# avr_g1000r_24.net
KiCad netlist of a schematic drawn in EAGLE
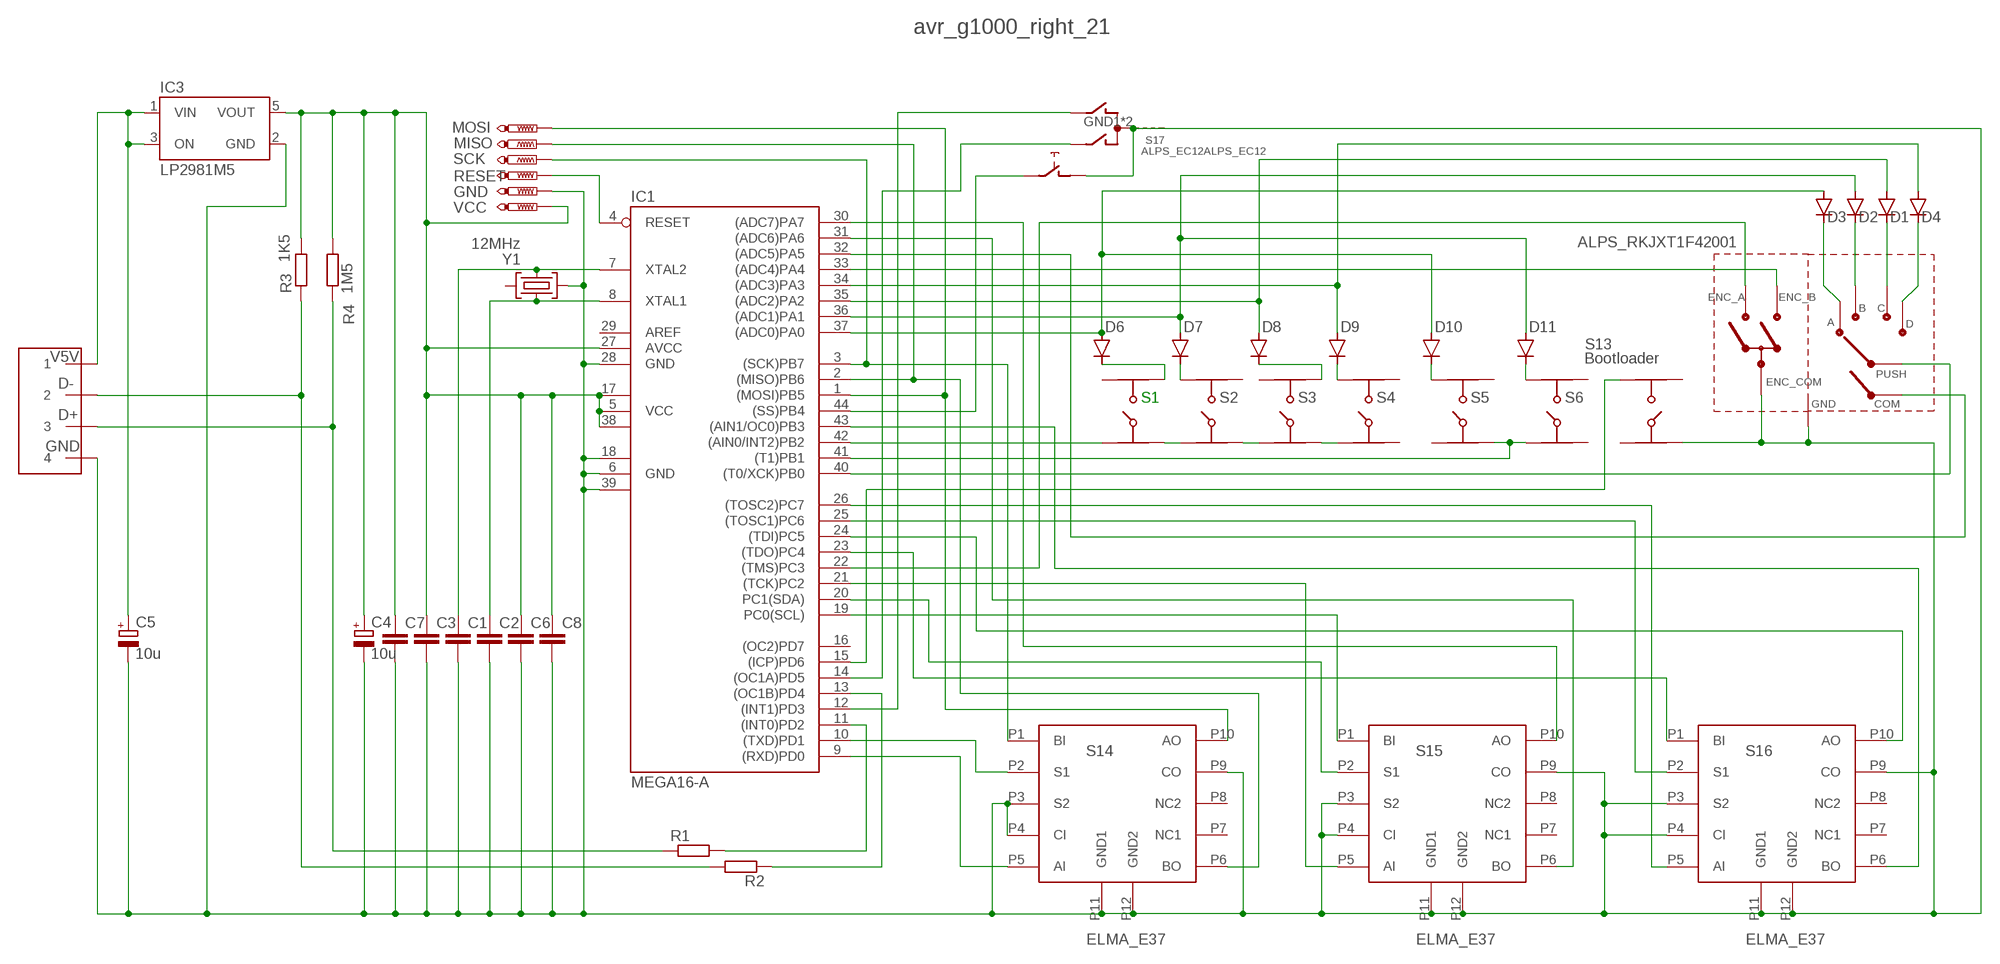
[diagram p0: schematic, sheet 1]

(export (version "E")
  (design (tool "Eeschema 10.0.6"))
  (components
    (comp (ref "C1")
      (value "C-EUC0402")
      (footprint "eagle-import:C0402")
      (libsource (lib "eagle-import") (part "C-EUC0402"))
    )
    (comp (ref "C2")
      (value "C-EUC0402")
      (footprint "eagle-import:C0402")
      (libsource (lib "eagle-import") (part "C-EUC0402"))
    )
    (comp (ref "C3")
      (value "C-EUC0402")
      (footprint "eagle-import:C0402")
      (libsource (lib "eagle-import") (part "C-EUC0402"))
    )
    (comp (ref "C4")
      (value "10u")
      (footprint "eagle-import:SMC_A")
      (libsource (lib "eagle-import") (part "CPOL-EUSMCA"))
    )
    (comp (ref "C5")
      (value "10u")
      (footprint "eagle-import:SMC_A")
      (libsource (lib "eagle-import") (part "CPOL-EUSMCA"))
    )
    (comp (ref "C6")
      (value "C-EUC0402")
      (footprint "eagle-import:C0402")
      (libsource (lib "eagle-import") (part "C-EUC0402"))
    )
    (comp (ref "C7")
      (value "C-EUC0402")
      (footprint "eagle-import:C0402")
      (libsource (lib "eagle-import") (part "C-EUC0402"))
    )
    (comp (ref "C8")
      (value "C-EUC0402")
      (footprint "eagle-import:C0402")
      (libsource (lib "eagle-import") (part "C-EUC0402"))
    )
    (comp (ref "D1")
      (value "DIODE-SOD123")
      (footprint "eagle-import:SOD123")
      (fields (field (name "SPICEPREFIX") "D"))
      (libsource (lib "eagle-import") (part "DIODE-SOD123"))
    )
    (comp (ref "D2")
      (value "DIODE-SOD123")
      (footprint "eagle-import:SOD123")
      (fields (field (name "SPICEPREFIX") "D"))
      (libsource (lib "eagle-import") (part "DIODE-SOD123"))
    )
    (comp (ref "D3")
      (value "DIODE-SOD123")
      (footprint "eagle-import:SOD123")
      (fields (field (name "SPICEPREFIX") "D"))
      (libsource (lib "eagle-import") (part "DIODE-SOD123"))
    )
    (comp (ref "D4")
      (value "DIODE-SOD123")
      (footprint "eagle-import:SOD123")
      (fields (field (name "SPICEPREFIX") "D"))
      (libsource (lib "eagle-import") (part "DIODE-SOD123"))
    )
    (comp (ref "D6")
      (value "DIODE-SOD123")
      (footprint "eagle-import:SOD123")
      (fields (field (name "SPICEPREFIX") "D"))
      (libsource (lib "eagle-import") (part "DIODE-SOD123"))
    )
    (comp (ref "D7")
      (value "DIODE-SOD123")
      (footprint "eagle-import:SOD123")
      (fields (field (name "SPICEPREFIX") "D"))
      (libsource (lib "eagle-import") (part "DIODE-SOD123"))
    )
    (comp (ref "D8")
      (value "DIODE-SOD123")
      (footprint "eagle-import:SOD123")
      (fields (field (name "SPICEPREFIX") "D"))
      (libsource (lib "eagle-import") (part "DIODE-SOD123"))
    )
    (comp (ref "D9")
      (value "DIODE-SOD123")
      (footprint "eagle-import:SOD123")
      (fields (field (name "SPICEPREFIX") "D"))
      (libsource (lib "eagle-import") (part "DIODE-SOD123"))
    )
    (comp (ref "D10")
      (value "DIODE-SOD123")
      (footprint "eagle-import:SOD123")
      (fields (field (name "SPICEPREFIX") "D"))
      (libsource (lib "eagle-import") (part "DIODE-SOD123"))
    )
    (comp (ref "D11")
      (value "DIODE-SOD123")
      (footprint "eagle-import:SOD123")
      (fields (field (name "SPICEPREFIX") "D"))
      (libsource (lib "eagle-import") (part "DIODE-SOD123"))
    )
    (comp (ref "GND")
      (value "PTR1TP10R")
      (footprint "eagle-import:TP10R")
      (libsource (lib "eagle-import") (part "PTR1TP10R"))
    )
    (comp (ref "IC1")
      (value "MEGA16-A")
      (footprint "eagle-import:TQFP44")
      (fields (field (name "MPN") "ATMEGA16-16AU"))
      (libsource (lib "eagle-import") (part "MEGA16-A"))
    )
    (comp (ref "IC3")
      (value "LP2981M5")
      (footprint "eagle-import:SOT23-5")
      (libsource (lib "eagle-import") (part "LP2981M5"))
    )
    (comp (ref "MISO")
      (value "PTR1TP10R")
      (footprint "eagle-import:TP10R")
      (libsource (lib "eagle-import") (part "PTR1TP10R"))
    )
    (comp (ref "MOSI")
      (value "PTR1TP10R")
      (footprint "eagle-import:TP10R")
      (libsource (lib "eagle-import") (part "PTR1TP10R"))
    )
    (comp (ref "R1")
      (value "R-EU_R0603")
      (footprint "eagle-import:R0603")
      (libsource (lib "eagle-import") (part "R-EU_R0603"))
    )
    (comp (ref "R2")
      (value "R-EU_R0603")
      (footprint "eagle-import:R0603")
      (libsource (lib "eagle-import") (part "R-EU_R0603"))
    )
    (comp (ref "R3")
      (value "1K5")
      (footprint "eagle-import:R0603")
      (libsource (lib "eagle-import") (part "R-EU_R0603"))
    )
    (comp (ref "R4")
      (value "1M5")
      (footprint "eagle-import:R0603")
      (libsource (lib "eagle-import") (part "R-EU_R0603"))
    )
    (comp (ref "RESET")
      (value "PTR1TP10R")
      (footprint "eagle-import:TP10R")
      (libsource (lib "eagle-import") (part "PTR1TP10R"))
    )
    (comp (ref "S1")
      (value "B3FS1000")
      (footprint "eagle-import:B3FS1000")
      (fields (field (name "SPICEPREFIX") "S"))
      (libsource (lib "eagle-import") (part "B3FS1000"))
    )
    (comp (ref "S2")
      (value "B3FS1000")
      (footprint "eagle-import:B3FS1000")
      (libsource (lib "eagle-import") (part "B3FS1000"))
    )
    (comp (ref "S3")
      (value "B3FS1000")
      (footprint "eagle-import:B3FS1000")
      (libsource (lib "eagle-import") (part "B3FS1000"))
    )
    (comp (ref "S4")
      (value "B3FS1000")
      (footprint "eagle-import:B3FS1000")
      (libsource (lib "eagle-import") (part "B3FS1000"))
    )
    (comp (ref "S5")
      (value "B3FS1000")
      (footprint "eagle-import:B3FS1000")
      (libsource (lib "eagle-import") (part "B3FS1000"))
    )
    (comp (ref "S6")
      (value "B3FS1000")
      (footprint "eagle-import:B3FS1000")
      (libsource (lib "eagle-import") (part "B3FS1000"))
    )
    (comp (ref "S7")
      (value "RKJXT1F42001")
      (footprint "eagle-import:RKJXT1F42001")
      (libsource (lib "eagle-import") (part "RKJXT1F42001"))
    )
    (comp (ref "S13")
      (value "Bootloader")
      (footprint "eagle-import:B3FS1000")
      (libsource (lib "eagle-import") (part "B3FS1000"))
    )
    (comp (ref "S14")
      (value "ELMA_E37")
      (footprint "eagle-import:ELMA_E37")
      (libsource (lib "eagle-import") (part "ELMA_E37"))
    )
    (comp (ref "S15")
      (value "ELMA_E37")
      (footprint "eagle-import:ELMA_E37")
      (libsource (lib "eagle-import") (part "ELMA_E37"))
    )
    (comp (ref "S16")
      (value "ELMA_E37")
      (footprint "eagle-import:ELMA_E37")
      (libsource (lib "eagle-import") (part "ELMA_E37"))
    )
    (comp (ref "S17")
      (value "ALPS_EC12ALPS_EC12")
      (footprint "eagle-import:ALPS_EC12E_SW")
      (libsource (lib "eagle-import") (part "ALPS_EC12ALPS_EC12"))
    )
    (comp (ref "SCK")
      (value "PTR1TP10R")
      (footprint "eagle-import:TP10R")
      (libsource (lib "eagle-import") (part "PTR1TP10R"))
    )
    (comp (ref "U$4")
      (value "HEADER4X1.27")
      (footprint "eagle-import:HEADER4X1.27")
      (libsource (lib "eagle-import") (part "HEADER4X1.27"))
    )
    (comp (ref "VCC")
      (value "PTR1TP10R")
      (footprint "eagle-import:TP10R")
      (libsource (lib "eagle-import") (part "PTR1TP10R"))
    )
    (comp (ref "Y1")
      (value "12MHz")
      (footprint "eagle-import:OSCCC500X320X100")
      (libsource (lib "eagle-import") (part "MJ-CRYSTALMJ"))
    )
  )
  (nets
    (net (code "1") (name "/D+") (class "Default")
      (node (ref "R1") (pin "1") (pinfunction "1_1") (pintype "passive"))
      (node (ref "R4") (pin "1") (pinfunction "1_1") (pintype "passive"))
      (node (ref "U$4") (pin "P3") (pinfunction "3_P3") (pintype "bidirectional"))
    )
    (net (code "2") (name "/D-") (class "Default")
      (node (ref "R2") (pin "2") (pinfunction "2_2") (pintype "passive"))
      (node (ref "R3") (pin "1") (pinfunction "1_1") (pintype "passive"))
      (node (ref "U$4") (pin "P2") (pinfunction "2_P2") (pintype "bidirectional"))
    )
    (net (code "3") (name "/GND") (class "Default")
      (node (ref "C1") (pin "2") (pinfunction "2_2") (pintype "passive"))
      (node (ref "C2") (pin "2") (pinfunction "2_2") (pintype "passive"))
      (node (ref "C3") (pin "2") (pinfunction "2_2") (pintype "passive"))
      (node (ref "C4") (pin "-") (pinfunction "-_-") (pintype "passive"))
      (node (ref "C5") (pin "-") (pinfunction "-_-") (pintype "passive"))
      (node (ref "C6") (pin "2") (pinfunction "2_2") (pintype "passive"))
      (node (ref "C7") (pin "2") (pinfunction "2_2") (pintype "passive"))
      (node (ref "C8") (pin "2") (pinfunction "2_2") (pintype "passive"))
      (node (ref "GND") (pin "TP") (pinfunction "TP_TP") (pintype "input"))
      (node (ref "IC1") (pin "18") (pinfunction "GND1_18") (pintype "power_in"))
      (node (ref "IC1") (pin "28") (pinfunction "GND_28") (pintype "power_in"))
      (node (ref "IC1") (pin "39") (pinfunction "GND2_39") (pintype "power_in"))
      (node (ref "IC1") (pin "6") (pinfunction "GND_6") (pintype "power_in"))
      (node (ref "IC3") (pin "2") (pinfunction "GND_2") (pintype "power_in"))
      (node (ref "S13") (pin "3") (pinfunction "3_3") (pintype "passive"))
      (node (ref "S14") (pin "P11") (pinfunction "GND1_P11") (pintype "bidirectional"))
      (node (ref "S14") (pin "P12") (pinfunction "GND2_P12") (pintype "bidirectional"))
      (node (ref "S14") (pin "P3") (pinfunction "S2_P3") (pintype "bidirectional"))
      (node (ref "S14") (pin "P4") (pinfunction "CI_P4") (pintype "bidirectional"))
      (node (ref "S14") (pin "P9") (pinfunction "CO_P9") (pintype "bidirectional"))
      (node (ref "S15") (pin "P11") (pinfunction "GND1_P11") (pintype "bidirectional"))
      (node (ref "S15") (pin "P12") (pinfunction "GND2_P12") (pintype "bidirectional"))
      (node (ref "S15") (pin "P3") (pinfunction "S2_P3") (pintype "bidirectional"))
      (node (ref "S15") (pin "P4") (pinfunction "CI_P4") (pintype "bidirectional"))
      (node (ref "S15") (pin "P9") (pinfunction "CO_P9") (pintype "bidirectional"))
      (node (ref "S16") (pin "P11") (pinfunction "GND1_P11") (pintype "bidirectional"))
      (node (ref "S16") (pin "P12") (pinfunction "GND2_P12") (pintype "bidirectional"))
      (node (ref "S16") (pin "P3") (pinfunction "S2_P3") (pintype "bidirectional"))
      (node (ref "S16") (pin "P4") (pinfunction "CI_P4") (pintype "bidirectional"))
      (node (ref "S16") (pin "P9") (pinfunction "CO_P9") (pintype "bidirectional"))
      (node (ref "S17") (pin "C") (pinfunction "C_C") (pintype "passive"))
      (node (ref "S17") (pin "D") (pinfunction "1_D") (pintype "passive"))
      (node (ref "S17") (pin "GND1") (pinfunction "G_GND1") (pintype "passive"))
      (node (ref "S17") (pin "GND2") (pinfunction "G_GND2") (pintype "passive"))
      (node (ref "S7") (pin "ENC_COM") (pinfunction "ENC_COM_ENC_COM") (pintype "passive"))
      (node (ref "S7") (pin "GND") (pinfunction "GND_GND") (pintype "passive"))
      (node (ref "U$4") (pin "P4") (pinfunction "4_P4") (pintype "bidirectional"))
      (node (ref "Y1") (pin "2") (pinfunction "GND1_2") (pintype "bidirectional"))
    )
    (net (code "4") (name "/PB2") (class "Default")
      (node (ref "IC1") (pin "42") (pinfunction "(AIN0/INT2)PB2_42") (pintype "bidirectional"))
      (node (ref "S1") (pin "3") (pinfunction "3_3") (pintype "passive"))
      (node (ref "S1") (pin "4") (pinfunction "4_4") (pintype "passive"))
      (node (ref "S2") (pin "3") (pinfunction "3_3") (pintype "passive"))
      (node (ref "S2") (pin "4") (pinfunction "4_4") (pintype "passive"))
      (node (ref "S3") (pin "3") (pinfunction "3_3") (pintype "passive"))
      (node (ref "S3") (pin "4") (pinfunction "4_4") (pintype "passive"))
      (node (ref "S4") (pin "3") (pinfunction "3_3") (pintype "passive"))
    )
    (net (code "5") (name "/V5V") (class "Default")
      (node (ref "C5") (pin "+") (pinfunction "+_+") (pintype "passive"))
      (node (ref "IC3") (pin "1") (pinfunction "VIN_1") (pintype "power_in"))
      (node (ref "IC3") (pin "3") (pinfunction "ON_3") (pintype "input"))
      (node (ref "U$4") (pin "P1") (pinfunction "1_P1") (pintype "bidirectional"))
    )
    (net (code "6") (name "Net-(D1-PadC)") (class "Default")
      (node (ref "D1") (pin "C") (pinfunction "C_C") (pintype "passive"))
      (node (ref "S7") (pin "C") (pinfunction "C_C") (pintype "passive"))
    )
    (net (code "7") (name "Net-(D2-PadC)") (class "Default")
      (node (ref "D2") (pin "C") (pinfunction "C_C") (pintype "passive"))
      (node (ref "S7") (pin "B") (pinfunction "B_B") (pintype "passive"))
    )
    (net (code "8") (name "Net-(D3-PadC)") (class "Default")
      (node (ref "D3") (pin "C") (pinfunction "C_C") (pintype "passive"))
      (node (ref "S7") (pin "A") (pinfunction "A_A") (pintype "passive"))
    )
    (net (code "9") (name "Net-(D4-PadC)") (class "Default")
      (node (ref "D4") (pin "C") (pinfunction "C_C") (pintype "passive"))
      (node (ref "S7") (pin "D") (pinfunction "D_D") (pintype "passive"))
    )
    (net (code "10") (name "Net-(D6-PadC)") (class "Default")
      (node (ref "D6") (pin "C") (pinfunction "C_C") (pintype "passive"))
      (node (ref "S1") (pin "2") (pinfunction "2_2") (pintype "passive"))
    )
    (net (code "11") (name "Net-(D7-PadC)") (class "Default")
      (node (ref "D7") (pin "C") (pinfunction "C_C") (pintype "passive"))
      (node (ref "S2") (pin "1") (pinfunction "1_1") (pintype "passive"))
    )
    (net (code "12") (name "Net-(D8-PadC)") (class "Default")
      (node (ref "D8") (pin "C") (pinfunction "C_C") (pintype "passive"))
      (node (ref "S3") (pin "2") (pinfunction "2_2") (pintype "passive"))
    )
    (net (code "13") (name "Net-(D9-PadC)") (class "Default")
      (node (ref "D9") (pin "C") (pinfunction "C_C") (pintype "passive"))
      (node (ref "S4") (pin "1") (pinfunction "1_1") (pintype "passive"))
    )
    (net (code "14") (name "Net-(D10-PadC)") (class "Default")
      (node (ref "D10") (pin "C") (pinfunction "C_C") (pintype "passive"))
      (node (ref "S5") (pin "1") (pinfunction "1_1") (pintype "passive"))
    )
    (net (code "15") (name "Net-(D11-PadC)") (class "Default")
      (node (ref "D11") (pin "C") (pinfunction "C_C") (pintype "passive"))
      (node (ref "S6") (pin "1") (pinfunction "1_1") (pintype "passive"))
    )
    (net (code "16") (name "Net-(IC1-(ADC0)PA0)") (class "Default")
      (node (ref "D10") (pin "A") (pinfunction "A_A") (pintype "passive"))
      (node (ref "D3") (pin "A") (pinfunction "A_A") (pintype "passive"))
      (node (ref "D6") (pin "A") (pinfunction "A_A") (pintype "passive"))
      (node (ref "IC1") (pin "37") (pinfunction "(ADC0)PA0_37") (pintype "bidirectional"))
    )
    (net (code "17") (name "Net-(IC1-(ADC1)PA1)") (class "Default")
      (node (ref "D11") (pin "A") (pinfunction "A_A") (pintype "passive"))
      (node (ref "D2") (pin "A") (pinfunction "A_A") (pintype "passive"))
      (node (ref "D7") (pin "A") (pinfunction "A_A") (pintype "passive"))
      (node (ref "IC1") (pin "36") (pinfunction "(ADC1)PA1_36") (pintype "bidirectional"))
    )
    (net (code "18") (name "Net-(IC1-(ADC2)PA2)") (class "Default")
      (node (ref "D1") (pin "A") (pinfunction "A_A") (pintype "passive"))
      (node (ref "D8") (pin "A") (pinfunction "A_A") (pintype "passive"))
      (node (ref "IC1") (pin "35") (pinfunction "(ADC2)PA2_35") (pintype "bidirectional"))
    )
    (net (code "19") (name "Net-(IC1-(ADC3)PA3)") (class "Default")
      (node (ref "D4") (pin "A") (pinfunction "A_A") (pintype "passive"))
      (node (ref "D9") (pin "A") (pinfunction "A_A") (pintype "passive"))
      (node (ref "IC1") (pin "34") (pinfunction "(ADC3)PA3_34") (pintype "bidirectional"))
    )
    (net (code "20") (name "Net-(IC1-(ADC4)PA4)") (class "Default")
      (node (ref "IC1") (pin "33") (pinfunction "(ADC4)PA4_33") (pintype "bidirectional"))
      (node (ref "S7") (pin "ENC_B") (pinfunction "ENC_B_ENC_B") (pintype "passive"))
    )
    (net (code "21") (name "Net-(IC1-(ADC5)PA5)") (class "Default")
      (node (ref "IC1") (pin "32") (pinfunction "(ADC5)PA5_32") (pintype "bidirectional"))
      (node (ref "S7") (pin "COM") (pinfunction "COM_COM") (pintype "passive"))
    )
    (net (code "22") (name "Net-(IC1-(ADC6)PA6)") (class "Default")
      (node (ref "IC1") (pin "31") (pinfunction "(ADC6)PA6_31") (pintype "bidirectional"))
      (node (ref "S15") (pin "P6") (pinfunction "BO_P6") (pintype "bidirectional"))
    )
    (net (code "23") (name "Net-(IC1-(ADC7)PA7)") (class "Default")
      (node (ref "IC1") (pin "30") (pinfunction "(ADC7)PA7_30") (pintype "bidirectional"))
      (node (ref "S15") (pin "P10") (pinfunction "AO_P10") (pintype "bidirectional"))
    )
    (net (code "24") (name "Net-(IC1-(AIN1{slash}OC0)PB3)") (class "Default")
      (node (ref "IC1") (pin "43") (pinfunction "(AIN1/OC0)PB3_43") (pintype "bidirectional"))
      (node (ref "S16") (pin "P6") (pinfunction "BO_P6") (pintype "bidirectional"))
    )
    (net (code "25") (name "Net-(IC1-(ICP)PD6)") (class "Default")
      (node (ref "IC1") (pin "15") (pinfunction "(ICP)PD6_15") (pintype "bidirectional"))
      (node (ref "S13") (pin "2") (pinfunction "2_2") (pintype "passive"))
    )
    (net (code "26") (name "Net-(IC1-(INT0)PD2)") (class "Default")
      (node (ref "IC1") (pin "11") (pinfunction "(INT0)PD2_11") (pintype "bidirectional"))
      (node (ref "R1") (pin "2") (pinfunction "2_2") (pintype "passive"))
    )
    (net (code "27") (name "Net-(IC1-(INT1)PD3)") (class "Default")
      (node (ref "IC1") (pin "12") (pinfunction "(INT1)PD3_12") (pintype "bidirectional"))
      (node (ref "S17") (pin "B") (pinfunction "B_B") (pintype "passive"))
    )
    (net (code "28") (name "Net-(IC1-(MISO)PB6)") (class "Default")
      (node (ref "IC1") (pin "2") (pinfunction "(MISO)PB6_2") (pintype "bidirectional"))
      (node (ref "MISO") (pin "TP") (pinfunction "TP_TP") (pintype "input"))
      (node (ref "S14") (pin "P6") (pinfunction "BO_P6") (pintype "bidirectional"))
    )
    (net (code "29") (name "Net-(IC1-(MOSI)PB5)") (class "Default")
      (node (ref "IC1") (pin "1") (pinfunction "(MOSI)PB5_1") (pintype "bidirectional"))
      (node (ref "MOSI") (pin "TP") (pinfunction "TP_TP") (pintype "input"))
      (node (ref "S14") (pin "P10") (pinfunction "AO_P10") (pintype "bidirectional"))
    )
    (net (code "30") (name "Net-(IC1-(OC1A)PD5)") (class "Default")
      (node (ref "IC1") (pin "14") (pinfunction "(OC1A)PD5_14") (pintype "bidirectional"))
      (node (ref "S17") (pin "A") (pinfunction "A_A") (pintype "passive"))
    )
    (net (code "31") (name "Net-(IC1-(OC1B)PD4)") (class "Default")
      (node (ref "IC1") (pin "13") (pinfunction "(OC1B)PD4_13") (pintype "bidirectional"))
      (node (ref "R2") (pin "1") (pinfunction "1_1") (pintype "passive"))
    )
    (net (code "32") (name "Net-(IC1-(RXD)PD0)") (class "Default")
      (node (ref "IC1") (pin "9") (pinfunction "(RXD)PD0_9") (pintype "bidirectional"))
      (node (ref "S14") (pin "P5") (pinfunction "AI_P5") (pintype "bidirectional"))
    )
    (net (code "33") (name "Net-(IC1-(SCK)PB7)") (class "Default")
      (node (ref "IC1") (pin "3") (pinfunction "(SCK)PB7_3") (pintype "bidirectional"))
      (node (ref "S14") (pin "P1") (pinfunction "BI_P1") (pintype "bidirectional"))
      (node (ref "SCK") (pin "TP") (pinfunction "TP_TP") (pintype "input"))
    )
    (net (code "34") (name "Net-(IC1-(SS)PB4)") (class "Default")
      (node (ref "IC1") (pin "44") (pinfunction "(SS)PB4_44") (pintype "bidirectional"))
      (node (ref "S17") (pin "E") (pinfunction "2_E") (pintype "passive"))
    )
    (net (code "35") (name "Net-(IC1-(T0{slash}XCK)PB0)") (class "Default")
      (node (ref "IC1") (pin "40") (pinfunction "(T0/XCK)PB0_40") (pintype "bidirectional"))
      (node (ref "S7") (pin "PUSH") (pinfunction "PUSH_PUSH") (pintype "passive"))
    )
    (net (code "36") (name "Net-(IC1-(T1)PB1)") (class "Default")
      (node (ref "IC1") (pin "41") (pinfunction "(T1)PB1_41") (pintype "bidirectional"))
      (node (ref "S5") (pin "4") (pinfunction "4_4") (pintype "passive"))
      (node (ref "S6") (pin "3") (pinfunction "3_3") (pintype "passive"))
    )
    (net (code "37") (name "Net-(IC1-(TCK)PC2)") (class "Default")
      (node (ref "IC1") (pin "21") (pinfunction "(TCK)PC2_21") (pintype "bidirectional"))
      (node (ref "S15") (pin "P5") (pinfunction "AI_P5") (pintype "bidirectional"))
    )
    (net (code "38") (name "Net-(IC1-(TDI)PC5)") (class "Default")
      (node (ref "IC1") (pin "24") (pinfunction "(TDI)PC5_24") (pintype "bidirectional"))
      (node (ref "S16") (pin "P10") (pinfunction "AO_P10") (pintype "bidirectional"))
    )
    (net (code "39") (name "Net-(IC1-(TDO)PC4)") (class "Default")
      (node (ref "IC1") (pin "23") (pinfunction "(TDO)PC4_23") (pintype "bidirectional"))
      (node (ref "S16") (pin "P1") (pinfunction "BI_P1") (pintype "bidirectional"))
    )
    (net (code "40") (name "Net-(IC1-(TMS)PC3)") (class "Default")
      (node (ref "IC1") (pin "22") (pinfunction "(TMS)PC3_22") (pintype "bidirectional"))
      (node (ref "S7") (pin "ENC_A") (pinfunction "ENC_A_ENC_A") (pintype "passive"))
    )
    (net (code "41") (name "Net-(IC1-(TOSC1)PC6)") (class "Default")
      (node (ref "IC1") (pin "25") (pinfunction "(TOSC1)PC6_25") (pintype "bidirectional"))
      (node (ref "S16") (pin "P2") (pinfunction "S1_P2") (pintype "bidirectional"))
    )
    (net (code "42") (name "Net-(IC1-(TOSC2)PC7)") (class "Default")
      (node (ref "IC1") (pin "26") (pinfunction "(TOSC2)PC7_26") (pintype "bidirectional"))
      (node (ref "S16") (pin "P5") (pinfunction "AI_P5") (pintype "bidirectional"))
    )
    (net (code "43") (name "Net-(IC1-(TXD)PD1)") (class "Default")
      (node (ref "IC1") (pin "10") (pinfunction "(TXD)PD1_10") (pintype "bidirectional"))
      (node (ref "S14") (pin "P2") (pinfunction "S1_P2") (pintype "bidirectional"))
    )
    (net (code "44") (name "Net-(IC1-AVCC)") (class "Default")
      (node (ref "C3") (pin "1") (pinfunction "1_1") (pintype "passive"))
      (node (ref "C4") (pin "+") (pinfunction "+_+") (pintype "passive"))
      (node (ref "C6") (pin "1") (pinfunction "1_1") (pintype "passive"))
      (node (ref "C7") (pin "1") (pinfunction "1_1") (pintype "passive"))
      (node (ref "C8") (pin "1") (pinfunction "1_1") (pintype "passive"))
      (node (ref "IC1") (pin "17") (pinfunction "VCC1_17") (pintype "power_in"))
      (node (ref "IC1") (pin "27") (pinfunction "AVCC_27") (pintype "power_in"))
      (node (ref "IC1") (pin "38") (pinfunction "VCC2_38") (pintype "power_in"))
      (node (ref "IC1") (pin "5") (pinfunction "VCC_5") (pintype "power_in"))
      (node (ref "IC3") (pin "5") (pinfunction "VOUT_5") (pintype "output"))
      (node (ref "R3") (pin "2") (pinfunction "2_2") (pintype "passive"))
      (node (ref "R4") (pin "2") (pinfunction "2_2") (pintype "passive"))
      (node (ref "VCC") (pin "TP") (pinfunction "TP_TP") (pintype "input"))
    )
    (net (code "45") (name "Net-(IC1-PC0(SCL))") (class "Default")
      (node (ref "IC1") (pin "19") (pinfunction "PC0(SCL)_19") (pintype "bidirectional"))
      (node (ref "S15") (pin "P1") (pinfunction "BI_P1") (pintype "bidirectional"))
    )
    (net (code "46") (name "Net-(IC1-PC1(SDA))") (class "Default")
      (node (ref "IC1") (pin "20") (pinfunction "PC1(SDA)_20") (pintype "bidirectional"))
      (node (ref "S15") (pin "P2") (pinfunction "S1_P2") (pintype "bidirectional"))
    )
    (net (code "47") (name "Net-(IC1-RESET)") (class "Default")
      (node (ref "IC1") (pin "4") (pinfunction "RESET_4") (pintype "input"))
      (node (ref "RESET") (pin "TP") (pinfunction "TP_TP") (pintype "input"))
    )
    (net (code "48") (name "Net-(IC1-XTAL1)") (class "Default")
      (node (ref "C2") (pin "1") (pinfunction "1_1") (pintype "passive"))
      (node (ref "IC1") (pin "8") (pinfunction "XTAL1_8") (pintype "bidirectional"))
      (node (ref "Y1") (pin "3") (pinfunction "CRYSTAL2_3") (pintype "bidirectional"))
    )
    (net (code "49") (name "Net-(IC1-XTAL2)") (class "Default")
      (node (ref "C1") (pin "1") (pinfunction "1_1") (pintype "passive"))
      (node (ref "IC1") (pin "7") (pinfunction "XTAL2_7") (pintype "bidirectional"))
      (node (ref "Y1") (pin "1") (pinfunction "CRYSTAL1_1") (pintype "bidirectional"))
    )
    (net (code "50") (name "unconnected-(IC1-(OC2)PD7-Pad16)") (class "Default")
      (node (ref "IC1") (pin "16") (pinfunction "(OC2)PD7_16") (pintype "bidirectional"))
    )
    (net (code "51") (name "unconnected-(IC1-AREF-Pad29)") (class "Default")
      (node (ref "IC1") (pin "29") (pinfunction "AREF_29") (pintype "passive"))
    )
    (net (code "52") (name "unconnected-(S1-Pad1)") (class "Default")
      (node (ref "S1") (pin "1") (pinfunction "1_1") (pintype "passive"))
    )
    (net (code "53") (name "unconnected-(S2-Pad2)") (class "Default")
      (node (ref "S2") (pin "2") (pinfunction "2_2") (pintype "passive"))
    )
    (net (code "54") (name "unconnected-(S3-Pad1)") (class "Default")
      (node (ref "S3") (pin "1") (pinfunction "1_1") (pintype "passive"))
    )
    (net (code "55") (name "unconnected-(S4-Pad2)") (class "Default")
      (node (ref "S4") (pin "2") (pinfunction "2_2") (pintype "passive"))
    )
    (net (code "56") (name "unconnected-(S4-Pad4)") (class "Default")
      (node (ref "S4") (pin "4") (pinfunction "4_4") (pintype "passive"))
    )
    (net (code "57") (name "unconnected-(S5-Pad2)") (class "Default")
      (node (ref "S5") (pin "2") (pinfunction "2_2") (pintype "passive"))
    )
    (net (code "58") (name "unconnected-(S5-Pad3)") (class "Default")
      (node (ref "S5") (pin "3") (pinfunction "3_3") (pintype "passive"))
    )
    (net (code "59") (name "unconnected-(S6-Pad2)") (class "Default")
      (node (ref "S6") (pin "2") (pinfunction "2_2") (pintype "passive"))
    )
    (net (code "60") (name "unconnected-(S6-Pad4)") (class "Default")
      (node (ref "S6") (pin "4") (pinfunction "4_4") (pintype "passive"))
    )
    (net (code "61") (name "unconnected-(S13-Pad1)") (class "Default")
      (node (ref "S13") (pin "1") (pinfunction "1_1") (pintype "passive"))
    )
    (net (code "62") (name "unconnected-(S13-Pad4)") (class "Default")
      (node (ref "S13") (pin "4") (pinfunction "4_4") (pintype "passive"))
    )
    (net (code "63") (name "unconnected-(S14-NC1-PadP7)") (class "Default")
      (node (ref "S14") (pin "P7") (pinfunction "NC1_P7") (pintype "no_connect"))
    )
    (net (code "64") (name "unconnected-(S14-NC2-PadP8)") (class "Default")
      (node (ref "S14") (pin "P8") (pinfunction "NC2_P8") (pintype "no_connect"))
    )
    (net (code "65") (name "unconnected-(S15-NC1-PadP7)") (class "Default")
      (node (ref "S15") (pin "P7") (pinfunction "NC1_P7") (pintype "no_connect"))
    )
    (net (code "66") (name "unconnected-(S15-NC2-PadP8)") (class "Default")
      (node (ref "S15") (pin "P8") (pinfunction "NC2_P8") (pintype "no_connect"))
    )
    (net (code "67") (name "unconnected-(S16-NC1-PadP7)") (class "Default")
      (node (ref "S16") (pin "P7") (pinfunction "NC1_P7") (pintype "no_connect"))
    )
    (net (code "68") (name "unconnected-(S16-NC2-PadP8)") (class "Default")
      (node (ref "S16") (pin "P8") (pinfunction "NC2_P8") (pintype "no_connect"))
    )
    (net (code "69") (name "unconnected-(Y1-GND2-Pad4)") (class "Default")
      (node (ref "Y1") (pin "4") (pinfunction "GND2_4") (pintype "bidirectional"))
    )
  )
)
